# design.net
KiCad netlist of a schematic drawn in Altium Designer
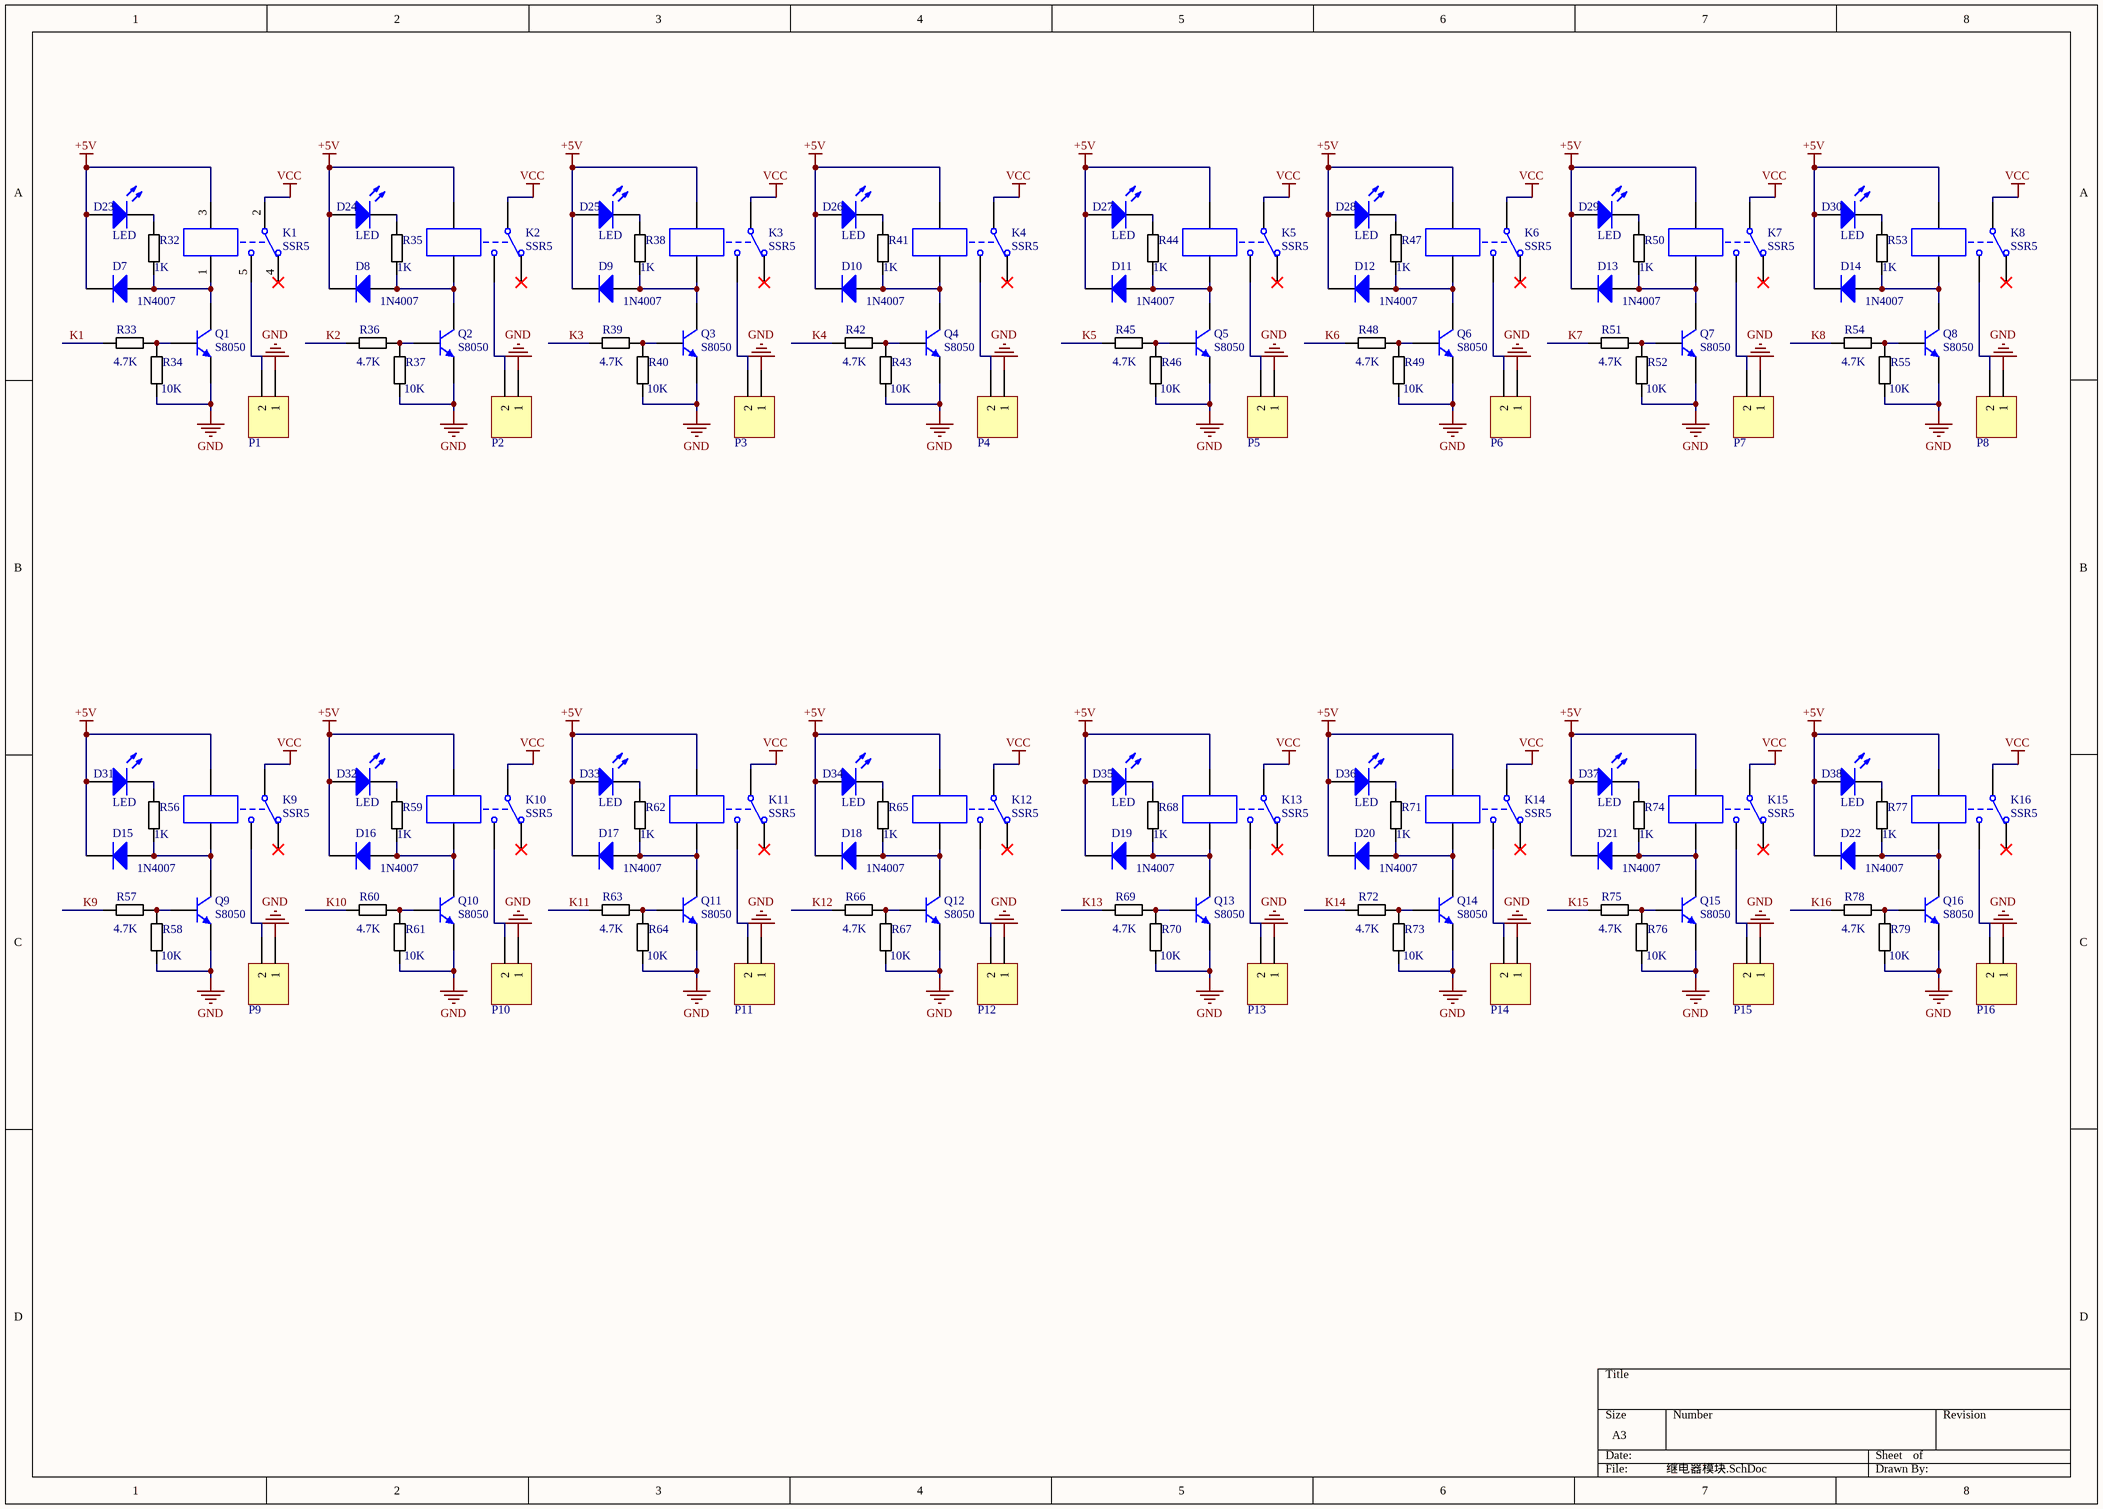
[diagram p0: 继电器模块.SchDoc]

(export (version "E")
  (design (tool "Eeschema 10.0.6"))
  (components
    (comp (ref "D7")
      (value "1N4007")
      (footprint "SMA")
      (description "1 Amp General Purpose Rectifier")
      (fields (field (name "PUBLISHER") "Altium Limited"))
      (libsource (lib "Sensor") (part "Diode 1N4007"))
    )
    (comp (ref "D8")
      (value "1N4007")
      (footprint "SMA")
      (description "1 Amp General Purpose Rectifier")
      (fields (field (name "PUBLISHER") "Altium Limited"))
      (libsource (lib "Sensor") (part "Diode 1N4007"))
    )
    (comp (ref "D9")
      (value "1N4007")
      (footprint "SMA")
      (description "1 Amp General Purpose Rectifier")
      (fields (field (name "PUBLISHER") "Altium Limited"))
      (libsource (lib "Sensor") (part "Diode 1N4007"))
    )
    (comp (ref "D10")
      (value "1N4007")
      (footprint "SMA")
      (description "1 Amp General Purpose Rectifier")
      (fields (field (name "PUBLISHER") "Altium Limited"))
      (libsource (lib "Sensor") (part "Diode 1N4007"))
    )
    (comp (ref "D11")
      (value "1N4007")
      (footprint "SMA")
      (description "1 Amp General Purpose Rectifier")
      (fields (field (name "PUBLISHER") "Altium Limited"))
      (libsource (lib "Sensor") (part "Diode 1N4007"))
    )
    (comp (ref "D12")
      (value "1N4007")
      (footprint "SMA")
      (description "1 Amp General Purpose Rectifier")
      (fields (field (name "PUBLISHER") "Altium Limited"))
      (libsource (lib "Sensor") (part "Diode 1N4007"))
    )
    (comp (ref "D13")
      (value "1N4007")
      (footprint "SMA")
      (description "1 Amp General Purpose Rectifier")
      (fields (field (name "PUBLISHER") "Altium Limited"))
      (libsource (lib "Sensor") (part "Diode 1N4007"))
    )
    (comp (ref "D14")
      (value "1N4007")
      (footprint "SMA")
      (description "1 Amp General Purpose Rectifier")
      (fields (field (name "PUBLISHER") "Altium Limited"))
      (libsource (lib "Sensor") (part "Diode 1N4007"))
    )
    (comp (ref "D15")
      (value "1N4007")
      (footprint "SMA")
      (description "1 Amp General Purpose Rectifier")
      (fields (field (name "PUBLISHER") "Altium Limited"))
      (libsource (lib "Sensor") (part "Diode 1N4007"))
    )
    (comp (ref "D16")
      (value "1N4007")
      (footprint "SMA")
      (description "1 Amp General Purpose Rectifier")
      (fields (field (name "PUBLISHER") "Altium Limited"))
      (libsource (lib "Sensor") (part "Diode 1N4007"))
    )
    (comp (ref "D17")
      (value "1N4007")
      (footprint "SMA")
      (description "1 Amp General Purpose Rectifier")
      (fields (field (name "PUBLISHER") "Altium Limited"))
      (libsource (lib "Sensor") (part "Diode 1N4007"))
    )
    (comp (ref "D18")
      (value "1N4007")
      (footprint "SMA")
      (description "1 Amp General Purpose Rectifier")
      (fields (field (name "PUBLISHER") "Altium Limited"))
      (libsource (lib "Sensor") (part "Diode 1N4007"))
    )
    (comp (ref "D19")
      (value "1N4007")
      (footprint "SMA")
      (description "1 Amp General Purpose Rectifier")
      (fields (field (name "PUBLISHER") "Altium Limited"))
      (libsource (lib "Sensor") (part "Diode 1N4007"))
    )
    (comp (ref "D20")
      (value "1N4007")
      (footprint "SMA")
      (description "1 Amp General Purpose Rectifier")
      (fields (field (name "PUBLISHER") "Altium Limited"))
      (libsource (lib "Sensor") (part "Diode 1N4007"))
    )
    (comp (ref "D21")
      (value "1N4007")
      (footprint "SMA")
      (description "1 Amp General Purpose Rectifier")
      (fields (field (name "PUBLISHER") "Altium Limited"))
      (libsource (lib "Sensor") (part "Diode 1N4007"))
    )
    (comp (ref "D22")
      (value "1N4007")
      (footprint "SMA")
      (description "1 Amp General Purpose Rectifier")
      (fields (field (name "PUBLISHER") "Altium Limited"))
      (libsource (lib "Sensor") (part "Diode 1N4007"))
    )
    (comp (ref "D23") (value "LED") (footprint "LED") (libsource (lib "Sensor") (part "LED")))
    (comp (ref "D24") (value "LED") (footprint "LED") (libsource (lib "Sensor") (part "LED")))
    (comp (ref "D25") (value "LED") (footprint "LED") (libsource (lib "Sensor") (part "LED")))
    (comp (ref "D26") (value "LED") (footprint "LED") (libsource (lib "Sensor") (part "LED")))
    (comp (ref "D27") (value "LED") (footprint "LED") (libsource (lib "Sensor") (part "LED")))
    (comp (ref "D28") (value "LED") (footprint "LED") (libsource (lib "Sensor") (part "LED")))
    (comp (ref "D29") (value "LED") (footprint "LED") (libsource (lib "Sensor") (part "LED")))
    (comp (ref "D30") (value "LED") (footprint "LED") (libsource (lib "Sensor") (part "LED")))
    (comp (ref "D31") (value "LED") (footprint "LED") (libsource (lib "Sensor") (part "LED")))
    (comp (ref "D32") (value "LED") (footprint "LED") (libsource (lib "Sensor") (part "LED")))
    (comp (ref "D33") (value "LED") (footprint "LED") (libsource (lib "Sensor") (part "LED")))
    (comp (ref "D34") (value "LED") (footprint "LED") (libsource (lib "Sensor") (part "LED")))
    (comp (ref "D35") (value "LED") (footprint "LED") (libsource (lib "Sensor") (part "LED")))
    (comp (ref "D36") (value "LED") (footprint "LED") (libsource (lib "Sensor") (part "LED")))
    (comp (ref "D37") (value "LED") (footprint "LED") (libsource (lib "Sensor") (part "LED")))
    (comp (ref "D38") (value "LED") (footprint "LED") (libsource (lib "Sensor") (part "LED")))
    (comp (ref "K1")
      (value "SSR5")
      (footprint "SSR-DC5")
      (fields (field (name "PUBLISHER") "Altium Limited"))
      (libsource (lib "") (part "SSR5_1"))
    )
    (comp (ref "K2")
      (value "SSR5")
      (footprint "SSR-DC5")
      (fields (field (name "PUBLISHER") "Altium Limited"))
      (libsource (lib "Power_5V_1A") (part "SSR5"))
    )
    (comp (ref "K3")
      (value "SSR5")
      (footprint "SSR-DC5")
      (fields (field (name "PUBLISHER") "Altium Limited"))
      (libsource (lib "Power_5V_1A") (part "SSR5"))
    )
    (comp (ref "K4")
      (value "SSR5")
      (footprint "SSR-DC5")
      (fields (field (name "PUBLISHER") "Altium Limited"))
      (libsource (lib "Power_5V_1A") (part "SSR5"))
    )
    (comp (ref "K5")
      (value "SSR5")
      (footprint "SSR-DC5")
      (fields (field (name "PUBLISHER") "Altium Limited"))
      (libsource (lib "Power_5V_1A") (part "SSR5"))
    )
    (comp (ref "K6")
      (value "SSR5")
      (footprint "SSR-DC5")
      (fields (field (name "PUBLISHER") "Altium Limited"))
      (libsource (lib "Power_5V_1A") (part "SSR5"))
    )
    (comp (ref "K7")
      (value "SSR5")
      (footprint "SSR-DC5")
      (fields (field (name "PUBLISHER") "Altium Limited"))
      (libsource (lib "Power_5V_1A") (part "SSR5"))
    )
    (comp (ref "K8")
      (value "SSR5")
      (footprint "SSR-DC5")
      (fields (field (name "PUBLISHER") "Altium Limited"))
      (libsource (lib "Power_5V_1A") (part "SSR5"))
    )
    (comp (ref "K9")
      (value "SSR5")
      (footprint "SSR-DC5")
      (fields (field (name "PUBLISHER") "Altium Limited"))
      (libsource (lib "Power_5V_1A") (part "SSR5"))
    )
    (comp (ref "K10")
      (value "SSR5")
      (footprint "SSR-DC5")
      (fields (field (name "PUBLISHER") "Altium Limited"))
      (libsource (lib "Power_5V_1A") (part "SSR5"))
    )
    (comp (ref "K11")
      (value "SSR5")
      (footprint "SSR-DC5")
      (fields (field (name "PUBLISHER") "Altium Limited"))
      (libsource (lib "Power_5V_1A") (part "SSR5"))
    )
    (comp (ref "K12")
      (value "SSR5")
      (footprint "SSR-DC5")
      (fields (field (name "PUBLISHER") "Altium Limited"))
      (libsource (lib "Power_5V_1A") (part "SSR5"))
    )
    (comp (ref "K13")
      (value "SSR5")
      (footprint "SSR-DC5")
      (fields (field (name "PUBLISHER") "Altium Limited"))
      (libsource (lib "Power_5V_1A") (part "SSR5"))
    )
    (comp (ref "K14")
      (value "SSR5")
      (footprint "SSR-DC5")
      (fields (field (name "PUBLISHER") "Altium Limited"))
      (libsource (lib "Power_5V_1A") (part "SSR5"))
    )
    (comp (ref "K15")
      (value "SSR5")
      (footprint "SSR-DC5")
      (fields (field (name "PUBLISHER") "Altium Limited"))
      (libsource (lib "Power_5V_1A") (part "SSR5"))
    )
    (comp (ref "K16")
      (value "SSR5")
      (footprint "SSR-DC5")
      (fields (field (name "PUBLISHER") "Altium Limited"))
      (libsource (lib "Power_5V_1A") (part "SSR5"))
    )
    (comp (ref "P1")
      (value "Header 2")
      (footprint "电源")
      (description "Header, 2-Pin")
      (fields (field (name "PUBLISHER") "Altium Limited"))
      (libsource (lib "Miscellaneous Connectors") (part "Header 2"))
    )
    (comp (ref "P2")
      (value "Header 2")
      (footprint "电源")
      (description "Header, 2-Pin")
      (fields (field (name "PUBLISHER") "Altium Limited"))
      (libsource (lib "Miscellaneous Connectors") (part "Header 2"))
    )
    (comp (ref "P3")
      (value "Header 2")
      (footprint "电源")
      (description "Header, 2-Pin")
      (fields (field (name "PUBLISHER") "Altium Limited"))
      (libsource (lib "Miscellaneous Connectors") (part "Header 2"))
    )
    (comp (ref "P4")
      (value "Header 2")
      (footprint "电源")
      (description "Header, 2-Pin")
      (fields (field (name "PUBLISHER") "Altium Limited"))
      (libsource (lib "Miscellaneous Connectors") (part "Header 2"))
    )
    (comp (ref "P5")
      (value "Header 2")
      (footprint "电源")
      (description "Header, 2-Pin")
      (fields (field (name "PUBLISHER") "Altium Limited"))
      (libsource (lib "Miscellaneous Connectors") (part "Header 2"))
    )
    (comp (ref "P6")
      (value "Header 2")
      (footprint "电源")
      (description "Header, 2-Pin")
      (fields (field (name "PUBLISHER") "Altium Limited"))
      (libsource (lib "Miscellaneous Connectors") (part "Header 2"))
    )
    (comp (ref "P7")
      (value "Header 2")
      (footprint "电源")
      (description "Header, 2-Pin")
      (fields (field (name "PUBLISHER") "Altium Limited"))
      (libsource (lib "Miscellaneous Connectors") (part "Header 2"))
    )
    (comp (ref "P8")
      (value "Header 2")
      (footprint "电源")
      (description "Header, 2-Pin")
      (fields (field (name "PUBLISHER") "Altium Limited"))
      (libsource (lib "Miscellaneous Connectors") (part "Header 2"))
    )
    (comp (ref "P9")
      (value "Header 2")
      (footprint "电源")
      (description "Header, 2-Pin")
      (fields (field (name "PUBLISHER") "Altium Limited"))
      (libsource (lib "Miscellaneous Connectors") (part "Header 2"))
    )
    (comp (ref "P10")
      (value "Header 2")
      (footprint "电源")
      (description "Header, 2-Pin")
      (fields (field (name "PUBLISHER") "Altium Limited"))
      (libsource (lib "Miscellaneous Connectors") (part "Header 2"))
    )
    (comp (ref "P11")
      (value "Header 2")
      (footprint "电源")
      (description "Header, 2-Pin")
      (fields (field (name "PUBLISHER") "Altium Limited"))
      (libsource (lib "Miscellaneous Connectors") (part "Header 2"))
    )
    (comp (ref "P12")
      (value "Header 2")
      (footprint "电源")
      (description "Header, 2-Pin")
      (fields (field (name "PUBLISHER") "Altium Limited"))
      (libsource (lib "Miscellaneous Connectors") (part "Header 2"))
    )
    (comp (ref "P13")
      (value "Header 2")
      (footprint "电源")
      (description "Header, 2-Pin")
      (fields (field (name "PUBLISHER") "Altium Limited"))
      (libsource (lib "Miscellaneous Connectors") (part "Header 2"))
    )
    (comp (ref "P14")
      (value "Header 2")
      (footprint "电源")
      (description "Header, 2-Pin")
      (fields (field (name "PUBLISHER") "Altium Limited"))
      (libsource (lib "Miscellaneous Connectors") (part "Header 2"))
    )
    (comp (ref "P15")
      (value "Header 2")
      (footprint "电源")
      (description "Header, 2-Pin")
      (fields (field (name "PUBLISHER") "Altium Limited"))
      (libsource (lib "Miscellaneous Connectors") (part "Header 2"))
    )
    (comp (ref "P16")
      (value "Header 2")
      (footprint "电源")
      (description "Header, 2-Pin")
      (fields (field (name "PUBLISHER") "Altium Limited"))
      (libsource (lib "Miscellaneous Connectors") (part "Header 2"))
    )
    (comp (ref "Q1") (value "S8050") (footprint "SOT-23") (libsource (lib "Sensor") (part "S8050")))
    (comp (ref "Q2") (value "S8050") (footprint "SOT-23") (libsource (lib "Sensor") (part "S8050")))
    (comp (ref "Q3") (value "S8050") (footprint "SOT-23") (libsource (lib "Sensor") (part "S8050")))
    (comp (ref "Q4") (value "S8050") (footprint "SOT-23") (libsource (lib "Sensor") (part "S8050")))
    (comp (ref "Q5") (value "S8050") (footprint "SOT-23") (libsource (lib "Sensor") (part "S8050")))
    (comp (ref "Q6") (value "S8050") (footprint "SOT-23") (libsource (lib "Sensor") (part "S8050")))
    (comp (ref "Q7") (value "S8050") (footprint "SOT-23") (libsource (lib "Sensor") (part "S8050")))
    (comp (ref "Q8") (value "S8050") (footprint "SOT-23") (libsource (lib "Sensor") (part "S8050")))
    (comp (ref "Q9") (value "S8050") (footprint "SOT-23") (libsource (lib "Sensor") (part "S8050")))
    (comp (ref "Q10") (value "S8050") (footprint "SOT-23") (libsource (lib "Sensor") (part "S8050")))
    (comp (ref "Q11") (value "S8050") (footprint "SOT-23") (libsource (lib "Sensor") (part "S8050")))
    (comp (ref "Q12") (value "S8050") (footprint "SOT-23") (libsource (lib "Sensor") (part "S8050")))
    (comp (ref "Q13") (value "S8050") (footprint "SOT-23") (libsource (lib "Sensor") (part "S8050")))
    (comp (ref "Q14") (value "S8050") (footprint "SOT-23") (libsource (lib "Sensor") (part "S8050")))
    (comp (ref "Q15") (value "S8050") (footprint "SOT-23") (libsource (lib "Sensor") (part "S8050")))
    (comp (ref "Q16") (value "S8050") (footprint "SOT-23") (libsource (lib "Sensor") (part "S8050")))
    (comp (ref "R32") (value "1K") (footprint "0603") (libsource (lib "") (part "RES-1K_2")))
    (comp (ref "R33") (value "4.7K") (footprint "0603") (libsource (lib "Sensor") (part "RES-1K")))
    (comp (ref "R34") (value "10K") (footprint "0603") (libsource (lib "") (part "RES-1K_1")))
    (comp (ref "R35") (value "1K") (footprint "0603") (libsource (lib "") (part "RES-1K_2")))
    (comp (ref "R36") (value "4.7K") (footprint "0603") (libsource (lib "Sensor") (part "RES-1K")))
    (comp (ref "R37") (value "10K") (footprint "0603") (libsource (lib "") (part "RES-1K_1")))
    (comp (ref "R38") (value "1K") (footprint "0603") (libsource (lib "") (part "RES-1K_2")))
    (comp (ref "R39") (value "4.7K") (footprint "0603") (libsource (lib "Sensor") (part "RES-1K")))
    (comp (ref "R40") (value "10K") (footprint "0603") (libsource (lib "") (part "RES-1K_1")))
    (comp (ref "R41") (value "1K") (footprint "0603") (libsource (lib "") (part "RES-1K_2")))
    (comp (ref "R42") (value "4.7K") (footprint "0603") (libsource (lib "Sensor") (part "RES-1K")))
    (comp (ref "R43") (value "10K") (footprint "0603") (libsource (lib "") (part "RES-1K_1")))
    (comp (ref "R44") (value "1K") (footprint "0603") (libsource (lib "") (part "RES-1K_2")))
    (comp (ref "R45") (value "4.7K") (footprint "0603") (libsource (lib "Sensor") (part "RES-1K")))
    (comp (ref "R46") (value "10K") (footprint "0603") (libsource (lib "") (part "RES-1K_1")))
    (comp (ref "R47") (value "1K") (footprint "0603") (libsource (lib "") (part "RES-1K_2")))
    (comp (ref "R48") (value "4.7K") (footprint "0603") (libsource (lib "Sensor") (part "RES-1K")))
    (comp (ref "R49") (value "10K") (footprint "0603") (libsource (lib "") (part "RES-1K_1")))
    (comp (ref "R50") (value "1K") (footprint "0603") (libsource (lib "") (part "RES-1K_2")))
    (comp (ref "R51") (value "4.7K") (footprint "0603") (libsource (lib "Sensor") (part "RES-1K")))
    (comp (ref "R52") (value "10K") (footprint "0603") (libsource (lib "") (part "RES-1K_1")))
    (comp (ref "R53") (value "1K") (footprint "0603") (libsource (lib "") (part "RES-1K_2")))
    (comp (ref "R54") (value "4.7K") (footprint "0603") (libsource (lib "Sensor") (part "RES-1K")))
    (comp (ref "R55") (value "10K") (footprint "0603") (libsource (lib "") (part "RES-1K_1")))
    (comp (ref "R56") (value "1K") (footprint "0603") (libsource (lib "") (part "RES-1K_2")))
    (comp (ref "R57") (value "4.7K") (footprint "0603") (libsource (lib "Sensor") (part "RES-1K")))
    (comp (ref "R58") (value "10K") (footprint "0603") (libsource (lib "") (part "RES-1K_1")))
    (comp (ref "R59") (value "1K") (footprint "0603") (libsource (lib "") (part "RES-1K_2")))
    (comp (ref "R60") (value "4.7K") (footprint "0603") (libsource (lib "Sensor") (part "RES-1K")))
    (comp (ref "R61") (value "10K") (footprint "0603") (libsource (lib "") (part "RES-1K_1")))
    (comp (ref "R62") (value "1K") (footprint "0603") (libsource (lib "") (part "RES-1K_2")))
    (comp (ref "R63") (value "4.7K") (footprint "0603") (libsource (lib "Sensor") (part "RES-1K")))
    (comp (ref "R64") (value "10K") (footprint "0603") (libsource (lib "") (part "RES-1K_1")))
    (comp (ref "R65") (value "1K") (footprint "0603") (libsource (lib "") (part "RES-1K_2")))
    (comp (ref "R66") (value "4.7K") (footprint "0603") (libsource (lib "Sensor") (part "RES-1K")))
    (comp (ref "R67") (value "10K") (footprint "0603") (libsource (lib "") (part "RES-1K_1")))
    (comp (ref "R68") (value "1K") (footprint "0603") (libsource (lib "") (part "RES-1K_2")))
    (comp (ref "R69") (value "4.7K") (footprint "0603") (libsource (lib "Sensor") (part "RES-1K")))
    (comp (ref "R70") (value "10K") (footprint "0603") (libsource (lib "") (part "RES-1K_1")))
    (comp (ref "R71") (value "1K") (footprint "0603") (libsource (lib "") (part "RES-1K_2")))
    (comp (ref "R72") (value "4.7K") (footprint "0603") (libsource (lib "Sensor") (part "RES-1K")))
    (comp (ref "R73") (value "10K") (footprint "0603") (libsource (lib "") (part "RES-1K_1")))
    (comp (ref "R74") (value "1K") (footprint "0603") (libsource (lib "") (part "RES-1K_2")))
    (comp (ref "R75") (value "4.7K") (footprint "0603") (libsource (lib "Sensor") (part "RES-1K")))
    (comp (ref "R76") (value "10K") (footprint "0603") (libsource (lib "") (part "RES-1K_1")))
    (comp (ref "R77") (value "1K") (footprint "0603") (libsource (lib "") (part "RES-1K_2")))
    (comp (ref "R78") (value "4.7K") (footprint "0603") (libsource (lib "Sensor") (part "RES-1K")))
    (comp (ref "R79") (value "10K") (footprint "0603") (libsource (lib "") (part "RES-1K_1")))
  )
  (nets
    (net (code "1") (name "+5V") (class "Default")
      (node (ref "D10") (pin "2") (pinfunction "K_2") (pintype "passive"))
      (node (ref "D11") (pin "2") (pinfunction "K_2") (pintype "passive"))
      (node (ref "D12") (pin "2") (pinfunction "K_2") (pintype "passive"))
      (node (ref "D13") (pin "2") (pinfunction "K_2") (pintype "passive"))
      (node (ref "D14") (pin "2") (pinfunction "K_2") (pintype "passive"))
      (node (ref "D15") (pin "2") (pinfunction "K_2") (pintype "passive"))
      (node (ref "D16") (pin "2") (pinfunction "K_2") (pintype "passive"))
      (node (ref "D17") (pin "2") (pinfunction "K_2") (pintype "passive"))
      (node (ref "D18") (pin "2") (pinfunction "K_2") (pintype "passive"))
      (node (ref "D19") (pin "2") (pinfunction "K_2") (pintype "passive"))
      (node (ref "D20") (pin "2") (pinfunction "K_2") (pintype "passive"))
      (node (ref "D21") (pin "2") (pinfunction "K_2") (pintype "passive"))
      (node (ref "D22") (pin "2") (pinfunction "K_2") (pintype "passive"))
      (node (ref "D23") (pin "1") (pinfunction "A_1") (pintype "passive"))
      (node (ref "D24") (pin "1") (pinfunction "A_1") (pintype "passive"))
      (node (ref "D25") (pin "1") (pinfunction "A_1") (pintype "passive"))
      (node (ref "D26") (pin "1") (pinfunction "A_1") (pintype "passive"))
      (node (ref "D27") (pin "1") (pinfunction "A_1") (pintype "passive"))
      (node (ref "D28") (pin "1") (pinfunction "A_1") (pintype "passive"))
      (node (ref "D29") (pin "1") (pinfunction "A_1") (pintype "passive"))
      (node (ref "D30") (pin "1") (pinfunction "A_1") (pintype "passive"))
      (node (ref "D31") (pin "1") (pinfunction "A_1") (pintype "passive"))
      (node (ref "D32") (pin "1") (pinfunction "A_1") (pintype "passive"))
      (node (ref "D33") (pin "1") (pinfunction "A_1") (pintype "passive"))
      (node (ref "D34") (pin "1") (pinfunction "A_1") (pintype "passive"))
      (node (ref "D35") (pin "1") (pinfunction "A_1") (pintype "passive"))
      (node (ref "D36") (pin "1") (pinfunction "A_1") (pintype "passive"))
      (node (ref "D37") (pin "1") (pinfunction "A_1") (pintype "passive"))
      (node (ref "D38") (pin "1") (pinfunction "A_1") (pintype "passive"))
      (node (ref "D7") (pin "2") (pinfunction "K_2") (pintype "passive"))
      (node (ref "D8") (pin "2") (pinfunction "K_2") (pintype "passive"))
      (node (ref "D9") (pin "2") (pinfunction "K_2") (pintype "passive"))
      (node (ref "K1") (pin "3") (pinfunction "3_3") (pintype "passive"))
      (node (ref "K10") (pin "3") (pinfunction "3_3") (pintype "passive"))
      (node (ref "K11") (pin "3") (pinfunction "3_3") (pintype "passive"))
      (node (ref "K12") (pin "3") (pinfunction "3_3") (pintype "passive"))
      (node (ref "K13") (pin "3") (pinfunction "3_3") (pintype "passive"))
      (node (ref "K14") (pin "3") (pinfunction "3_3") (pintype "passive"))
      (node (ref "K15") (pin "3") (pinfunction "3_3") (pintype "passive"))
      (node (ref "K16") (pin "3") (pinfunction "3_3") (pintype "passive"))
      (node (ref "K2") (pin "3") (pinfunction "3_3") (pintype "passive"))
      (node (ref "K3") (pin "3") (pinfunction "3_3") (pintype "passive"))
      (node (ref "K4") (pin "3") (pinfunction "3_3") (pintype "passive"))
      (node (ref "K5") (pin "3") (pinfunction "3_3") (pintype "passive"))
      (node (ref "K6") (pin "3") (pinfunction "3_3") (pintype "passive"))
      (node (ref "K7") (pin "3") (pinfunction "3_3") (pintype "passive"))
      (node (ref "K8") (pin "3") (pinfunction "3_3") (pintype "passive"))
      (node (ref "K9") (pin "3") (pinfunction "3_3") (pintype "passive"))
    )
    (net (code "2") (name "/K1") (class "Default")
      (node (ref "R33") (pin "2") (pinfunction "2_2") (pintype "passive"))
    )
    (net (code "3") (name "/K2") (class "Default")
      (node (ref "R36") (pin "2") (pinfunction "2_2") (pintype "passive"))
    )
    (net (code "4") (name "/K3") (class "Default")
      (node (ref "R39") (pin "2") (pinfunction "2_2") (pintype "passive"))
    )
    (net (code "5") (name "/K4") (class "Default")
      (node (ref "R42") (pin "2") (pinfunction "2_2") (pintype "passive"))
    )
    (net (code "6") (name "/K5") (class "Default")
      (node (ref "R45") (pin "2") (pinfunction "2_2") (pintype "passive"))
    )
    (net (code "7") (name "/K6") (class "Default")
      (node (ref "R48") (pin "2") (pinfunction "2_2") (pintype "passive"))
    )
    (net (code "8") (name "/K7") (class "Default")
      (node (ref "R51") (pin "2") (pinfunction "2_2") (pintype "passive"))
    )
    (net (code "9") (name "/K8") (class "Default")
      (node (ref "R54") (pin "2") (pinfunction "2_2") (pintype "passive"))
    )
    (net (code "10") (name "/K9") (class "Default")
      (node (ref "R57") (pin "2") (pinfunction "2_2") (pintype "passive"))
    )
    (net (code "11") (name "/K10") (class "Default")
      (node (ref "R60") (pin "2") (pinfunction "2_2") (pintype "passive"))
    )
    (net (code "12") (name "/K11") (class "Default")
      (node (ref "R63") (pin "2") (pinfunction "2_2") (pintype "passive"))
    )
    (net (code "13") (name "/K12") (class "Default")
      (node (ref "R66") (pin "2") (pinfunction "2_2") (pintype "passive"))
    )
    (net (code "14") (name "/K13") (class "Default")
      (node (ref "R69") (pin "2") (pinfunction "2_2") (pintype "passive"))
    )
    (net (code "15") (name "/K14") (class "Default")
      (node (ref "R72") (pin "2") (pinfunction "2_2") (pintype "passive"))
    )
    (net (code "16") (name "/K15") (class "Default")
      (node (ref "R75") (pin "2") (pinfunction "2_2") (pintype "passive"))
    )
    (net (code "17") (name "/K16") (class "Default")
      (node (ref "R78") (pin "2") (pinfunction "2_2") (pintype "passive"))
    )
    (net (code "18") (name "GND") (class "Default")
      (node (ref "P1") (pin "1") (pinfunction "1_1") (pintype "passive"))
      (node (ref "P10") (pin "1") (pinfunction "1_1") (pintype "passive"))
      (node (ref "P11") (pin "1") (pinfunction "1_1") (pintype "passive"))
      (node (ref "P12") (pin "1") (pinfunction "1_1") (pintype "passive"))
      (node (ref "P13") (pin "1") (pinfunction "1_1") (pintype "passive"))
      (node (ref "P14") (pin "1") (pinfunction "1_1") (pintype "passive"))
      (node (ref "P15") (pin "1") (pinfunction "1_1") (pintype "passive"))
      (node (ref "P16") (pin "1") (pinfunction "1_1") (pintype "passive"))
      (node (ref "P2") (pin "1") (pinfunction "1_1") (pintype "passive"))
      (node (ref "P3") (pin "1") (pinfunction "1_1") (pintype "passive"))
      (node (ref "P4") (pin "1") (pinfunction "1_1") (pintype "passive"))
      (node (ref "P5") (pin "1") (pinfunction "1_1") (pintype "passive"))
      (node (ref "P6") (pin "1") (pinfunction "1_1") (pintype "passive"))
      (node (ref "P7") (pin "1") (pinfunction "1_1") (pintype "passive"))
      (node (ref "P8") (pin "1") (pinfunction "1_1") (pintype "passive"))
      (node (ref "P9") (pin "1") (pinfunction "1_1") (pintype "passive"))
      (node (ref "Q1") (pin "2") (pinfunction "E_2") (pintype "passive"))
      (node (ref "Q10") (pin "2") (pinfunction "E_2") (pintype "passive"))
      (node (ref "Q11") (pin "2") (pinfunction "E_2") (pintype "passive"))
      (node (ref "Q12") (pin "2") (pinfunction "E_2") (pintype "passive"))
      (node (ref "Q13") (pin "2") (pinfunction "E_2") (pintype "passive"))
      (node (ref "Q14") (pin "2") (pinfunction "E_2") (pintype "passive"))
      (node (ref "Q15") (pin "2") (pinfunction "E_2") (pintype "passive"))
      (node (ref "Q16") (pin "2") (pinfunction "E_2") (pintype "passive"))
      (node (ref "Q2") (pin "2") (pinfunction "E_2") (pintype "passive"))
      (node (ref "Q3") (pin "2") (pinfunction "E_2") (pintype "passive"))
      (node (ref "Q4") (pin "2") (pinfunction "E_2") (pintype "passive"))
      (node (ref "Q5") (pin "2") (pinfunction "E_2") (pintype "passive"))
      (node (ref "Q6") (pin "2") (pinfunction "E_2") (pintype "passive"))
      (node (ref "Q7") (pin "2") (pinfunction "E_2") (pintype "passive"))
      (node (ref "Q8") (pin "2") (pinfunction "E_2") (pintype "passive"))
      (node (ref "Q9") (pin "2") (pinfunction "E_2") (pintype "passive"))
      (node (ref "R34") (pin "2") (pinfunction "2_2") (pintype "passive"))
      (node (ref "R37") (pin "2") (pinfunction "2_2") (pintype "passive"))
      (node (ref "R40") (pin "2") (pinfunction "2_2") (pintype "passive"))
      (node (ref "R43") (pin "2") (pinfunction "2_2") (pintype "passive"))
      (node (ref "R46") (pin "2") (pinfunction "2_2") (pintype "passive"))
      (node (ref "R49") (pin "2") (pinfunction "2_2") (pintype "passive"))
      (node (ref "R52") (pin "2") (pinfunction "2_2") (pintype "passive"))
      (node (ref "R55") (pin "2") (pinfunction "2_2") (pintype "passive"))
      (node (ref "R58") (pin "2") (pinfunction "2_2") (pintype "passive"))
      (node (ref "R61") (pin "2") (pinfunction "2_2") (pintype "passive"))
      (node (ref "R64") (pin "2") (pinfunction "2_2") (pintype "passive"))
      (node (ref "R67") (pin "2") (pinfunction "2_2") (pintype "passive"))
      (node (ref "R70") (pin "2") (pinfunction "2_2") (pintype "passive"))
      (node (ref "R73") (pin "2") (pinfunction "2_2") (pintype "passive"))
      (node (ref "R76") (pin "2") (pinfunction "2_2") (pintype "passive"))
      (node (ref "R79") (pin "2") (pinfunction "2_2") (pintype "passive"))
    )
    (net (code "19") (name "Net-(D7-A)") (class "Default")
      (node (ref "D7") (pin "1") (pinfunction "A_1") (pintype "passive"))
      (node (ref "K1") (pin "1") (pinfunction "1_1") (pintype "passive"))
      (node (ref "Q1") (pin "3") (pinfunction "C_3") (pintype "passive"))
      (node (ref "R32") (pin "1") (pinfunction "1_1") (pintype "passive"))
    )
    (net (code "20") (name "Net-(D8-A)") (class "Default")
      (node (ref "D8") (pin "1") (pinfunction "A_1") (pintype "passive"))
      (node (ref "K2") (pin "1") (pinfunction "1_1") (pintype "passive"))
      (node (ref "Q2") (pin "3") (pinfunction "C_3") (pintype "passive"))
      (node (ref "R35") (pin "1") (pinfunction "1_1") (pintype "passive"))
    )
    (net (code "21") (name "Net-(D9-A)") (class "Default")
      (node (ref "D9") (pin "1") (pinfunction "A_1") (pintype "passive"))
      (node (ref "K3") (pin "1") (pinfunction "1_1") (pintype "passive"))
      (node (ref "Q3") (pin "3") (pinfunction "C_3") (pintype "passive"))
      (node (ref "R38") (pin "1") (pinfunction "1_1") (pintype "passive"))
    )
    (net (code "22") (name "Net-(D10-A)") (class "Default")
      (node (ref "D10") (pin "1") (pinfunction "A_1") (pintype "passive"))
      (node (ref "K4") (pin "1") (pinfunction "1_1") (pintype "passive"))
      (node (ref "Q4") (pin "3") (pinfunction "C_3") (pintype "passive"))
      (node (ref "R41") (pin "1") (pinfunction "1_1") (pintype "passive"))
    )
    (net (code "23") (name "Net-(D11-A)") (class "Default")
      (node (ref "D11") (pin "1") (pinfunction "A_1") (pintype "passive"))
      (node (ref "K5") (pin "1") (pinfunction "1_1") (pintype "passive"))
      (node (ref "Q5") (pin "3") (pinfunction "C_3") (pintype "passive"))
      (node (ref "R44") (pin "1") (pinfunction "1_1") (pintype "passive"))
    )
    (net (code "24") (name "Net-(D12-A)") (class "Default")
      (node (ref "D12") (pin "1") (pinfunction "A_1") (pintype "passive"))
      (node (ref "K6") (pin "1") (pinfunction "1_1") (pintype "passive"))
      (node (ref "Q6") (pin "3") (pinfunction "C_3") (pintype "passive"))
      (node (ref "R47") (pin "1") (pinfunction "1_1") (pintype "passive"))
    )
    (net (code "25") (name "Net-(D13-A)") (class "Default")
      (node (ref "D13") (pin "1") (pinfunction "A_1") (pintype "passive"))
      (node (ref "K7") (pin "1") (pinfunction "1_1") (pintype "passive"))
      (node (ref "Q7") (pin "3") (pinfunction "C_3") (pintype "passive"))
      (node (ref "R50") (pin "1") (pinfunction "1_1") (pintype "passive"))
    )
    (net (code "26") (name "Net-(D14-A)") (class "Default")
      (node (ref "D14") (pin "1") (pinfunction "A_1") (pintype "passive"))
      (node (ref "K8") (pin "1") (pinfunction "1_1") (pintype "passive"))
      (node (ref "Q8") (pin "3") (pinfunction "C_3") (pintype "passive"))
      (node (ref "R53") (pin "1") (pinfunction "1_1") (pintype "passive"))
    )
    (net (code "27") (name "Net-(D15-A)") (class "Default")
      (node (ref "D15") (pin "1") (pinfunction "A_1") (pintype "passive"))
      (node (ref "K9") (pin "1") (pinfunction "1_1") (pintype "passive"))
      (node (ref "Q9") (pin "3") (pinfunction "C_3") (pintype "passive"))
      (node (ref "R56") (pin "1") (pinfunction "1_1") (pintype "passive"))
    )
    (net (code "28") (name "Net-(D16-A)") (class "Default")
      (node (ref "D16") (pin "1") (pinfunction "A_1") (pintype "passive"))
      (node (ref "K10") (pin "1") (pinfunction "1_1") (pintype "passive"))
      (node (ref "Q10") (pin "3") (pinfunction "C_3") (pintype "passive"))
      (node (ref "R59") (pin "1") (pinfunction "1_1") (pintype "passive"))
    )
    (net (code "29") (name "Net-(D17-A)") (class "Default")
      (node (ref "D17") (pin "1") (pinfunction "A_1") (pintype "passive"))
      (node (ref "K11") (pin "1") (pinfunction "1_1") (pintype "passive"))
      (node (ref "Q11") (pin "3") (pinfunction "C_3") (pintype "passive"))
      (node (ref "R62") (pin "1") (pinfunction "1_1") (pintype "passive"))
    )
    (net (code "30") (name "Net-(D18-A)") (class "Default")
      (node (ref "D18") (pin "1") (pinfunction "A_1") (pintype "passive"))
      (node (ref "K12") (pin "1") (pinfunction "1_1") (pintype "passive"))
      (node (ref "Q12") (pin "3") (pinfunction "C_3") (pintype "passive"))
      (node (ref "R65") (pin "1") (pinfunction "1_1") (pintype "passive"))
    )
    (net (code "31") (name "Net-(D19-A)") (class "Default")
      (node (ref "D19") (pin "1") (pinfunction "A_1") (pintype "passive"))
      (node (ref "K13") (pin "1") (pinfunction "1_1") (pintype "passive"))
      (node (ref "Q13") (pin "3") (pinfunction "C_3") (pintype "passive"))
      (node (ref "R68") (pin "1") (pinfunction "1_1") (pintype "passive"))
    )
    (net (code "32") (name "Net-(D20-A)") (class "Default")
      (node (ref "D20") (pin "1") (pinfunction "A_1") (pintype "passive"))
      (node (ref "K14") (pin "1") (pinfunction "1_1") (pintype "passive"))
      (node (ref "Q14") (pin "3") (pinfunction "C_3") (pintype "passive"))
      (node (ref "R71") (pin "1") (pinfunction "1_1") (pintype "passive"))
    )
    (net (code "33") (name "Net-(D21-A)") (class "Default")
      (node (ref "D21") (pin "1") (pinfunction "A_1") (pintype "passive"))
      (node (ref "K15") (pin "1") (pinfunction "1_1") (pintype "passive"))
      (node (ref "Q15") (pin "3") (pinfunction "C_3") (pintype "passive"))
      (node (ref "R74") (pin "1") (pinfunction "1_1") (pintype "passive"))
    )
    (net (code "34") (name "Net-(D22-A)") (class "Default")
      (node (ref "D22") (pin "1") (pinfunction "A_1") (pintype "passive"))
      (node (ref "K16") (pin "1") (pinfunction "1_1") (pintype "passive"))
      (node (ref "Q16") (pin "3") (pinfunction "C_3") (pintype "passive"))
      (node (ref "R77") (pin "1") (pinfunction "1_1") (pintype "passive"))
    )
    (net (code "35") (name "Net-(D23-K)") (class "Default")
      (node (ref "D23") (pin "2") (pinfunction "K_2") (pintype "passive"))
      (node (ref "R32") (pin "2") (pinfunction "2_2") (pintype "passive"))
    )
    (net (code "36") (name "Net-(D24-K)") (class "Default")
      (node (ref "D24") (pin "2") (pinfunction "K_2") (pintype "passive"))
      (node (ref "R35") (pin "2") (pinfunction "2_2") (pintype "passive"))
    )
    (net (code "37") (name "Net-(D25-K)") (class "Default")
      (node (ref "D25") (pin "2") (pinfunction "K_2") (pintype "passive"))
      (node (ref "R38") (pin "2") (pinfunction "2_2") (pintype "passive"))
    )
    (net (code "38") (name "Net-(D26-K)") (class "Default")
      (node (ref "D26") (pin "2") (pinfunction "K_2") (pintype "passive"))
      (node (ref "R41") (pin "2") (pinfunction "2_2") (pintype "passive"))
    )
    (net (code "39") (name "Net-(D27-K)") (class "Default")
      (node (ref "D27") (pin "2") (pinfunction "K_2") (pintype "passive"))
      (node (ref "R44") (pin "2") (pinfunction "2_2") (pintype "passive"))
    )
    (net (code "40") (name "Net-(D28-K)") (class "Default")
      (node (ref "D28") (pin "2") (pinfunction "K_2") (pintype "passive"))
      (node (ref "R47") (pin "2") (pinfunction "2_2") (pintype "passive"))
    )
    (net (code "41") (name "Net-(D29-K)") (class "Default")
      (node (ref "D29") (pin "2") (pinfunction "K_2") (pintype "passive"))
      (node (ref "R50") (pin "2") (pinfunction "2_2") (pintype "passive"))
    )
    (net (code "42") (name "Net-(D30-K)") (class "Default")
      (node (ref "D30") (pin "2") (pinfunction "K_2") (pintype "passive"))
      (node (ref "R53") (pin "2") (pinfunction "2_2") (pintype "passive"))
    )
    (net (code "43") (name "Net-(D31-K)") (class "Default")
      (node (ref "D31") (pin "2") (pinfunction "K_2") (pintype "passive"))
      (node (ref "R56") (pin "2") (pinfunction "2_2") (pintype "passive"))
    )
    (net (code "44") (name "Net-(D32-K)") (class "Default")
      (node (ref "D32") (pin "2") (pinfunction "K_2") (pintype "passive"))
      (node (ref "R59") (pin "2") (pinfunction "2_2") (pintype "passive"))
    )
    (net (code "45") (name "Net-(D33-K)") (class "Default")
      (node (ref "D33") (pin "2") (pinfunction "K_2") (pintype "passive"))
      (node (ref "R62") (pin "2") (pinfunction "2_2") (pintype "passive"))
    )
    (net (code "46") (name "Net-(D34-K)") (class "Default")
      (node (ref "D34") (pin "2") (pinfunction "K_2") (pintype "passive"))
      (node (ref "R65") (pin "2") (pinfunction "2_2") (pintype "passive"))
    )
    (net (code "47") (name "Net-(D35-K)") (class "Default")
      (node (ref "D35") (pin "2") (pinfunction "K_2") (pintype "passive"))
      (node (ref "R68") (pin "2") (pinfunction "2_2") (pintype "passive"))
    )
    (net (code "48") (name "Net-(D36-K)") (class "Default")
      (node (ref "D36") (pin "2") (pinfunction "K_2") (pintype "passive"))
      (node (ref "R71") (pin "2") (pinfunction "2_2") (pintype "passive"))
    )
    (net (code "49") (name "Net-(D37-K)") (class "Default")
      (node (ref "D37") (pin "2") (pinfunction "K_2") (pintype "passive"))
      (node (ref "R74") (pin "2") (pinfunction "2_2") (pintype "passive"))
    )
    (net (code "50") (name "Net-(D38-K)") (class "Default")
      (node (ref "D38") (pin "2") (pinfunction "K_2") (pintype "passive"))
      (node (ref "R77") (pin "2") (pinfunction "2_2") (pintype "passive"))
    )
    (net (code "51") (name "Net-(K1-Pad5)") (class "Default")
      (node (ref "K1") (pin "5") (pinfunction "5_5") (pintype "passive"))
      (node (ref "P1") (pin "2") (pinfunction "2_2") (pintype "passive"))
    )
    (net (code "52") (name "Net-(K2-Pad5)") (class "Default")
      (node (ref "K2") (pin "5") (pinfunction "5_5") (pintype "passive"))
      (node (ref "P2") (pin "2") (pinfunction "2_2") (pintype "passive"))
    )
    (net (code "53") (name "Net-(K3-Pad5)") (class "Default")
      (node (ref "K3") (pin "5") (pinfunction "5_5") (pintype "passive"))
      (node (ref "P3") (pin "2") (pinfunction "2_2") (pintype "passive"))
    )
    (net (code "54") (name "Net-(K4-Pad5)") (class "Default")
      (node (ref "K4") (pin "5") (pinfunction "5_5") (pintype "passive"))
      (node (ref "P4") (pin "2") (pinfunction "2_2") (pintype "passive"))
    )
    (net (code "55") (name "Net-(K5-Pad5)") (class "Default")
      (node (ref "K5") (pin "5") (pinfunction "5_5") (pintype "passive"))
      (node (ref "P5") (pin "2") (pinfunction "2_2") (pintype "passive"))
    )
    (net (code "56") (name "Net-(K6-Pad5)") (class "Default")
      (node (ref "K6") (pin "5") (pinfunction "5_5") (pintype "passive"))
      (node (ref "P6") (pin "2") (pinfunction "2_2") (pintype "passive"))
    )
    (net (code "57") (name "Net-(K7-Pad5)") (class "Default")
      (node (ref "K7") (pin "5") (pinfunction "5_5") (pintype "passive"))
      (node (ref "P7") (pin "2") (pinfunction "2_2") (pintype "passive"))
    )
    (net (code "58") (name "Net-(K8-Pad5)") (class "Default")
      (node (ref "K8") (pin "5") (pinfunction "5_5") (pintype "passive"))
      (node (ref "P8") (pin "2") (pinfunction "2_2") (pintype "passive"))
    )
    (net (code "59") (name "Net-(K9-Pad5)") (class "Default")
      (node (ref "K9") (pin "5") (pinfunction "5_5") (pintype "passive"))
      (node (ref "P9") (pin "2") (pinfunction "2_2") (pintype "passive"))
    )
    (net (code "60") (name "Net-(K10-Pad5)") (class "Default")
      (node (ref "K10") (pin "5") (pinfunction "5_5") (pintype "passive"))
      (node (ref "P10") (pin "2") (pinfunction "2_2") (pintype "passive"))
    )
    (net (code "61") (name "Net-(K11-Pad5)") (class "Default")
      (node (ref "K11") (pin "5") (pinfunction "5_5") (pintype "passive"))
      (node (ref "P11") (pin "2") (pinfunction "2_2") (pintype "passive"))
    )
    (net (code "62") (name "Net-(K12-Pad5)") (class "Default")
      (node (ref "K12") (pin "5") (pinfunction "5_5") (pintype "passive"))
      (node (ref "P12") (pin "2") (pinfunction "2_2") (pintype "passive"))
    )
    (net (code "63") (name "Net-(K13-Pad5)") (class "Default")
      (node (ref "K13") (pin "5") (pinfunction "5_5") (pintype "passive"))
      (node (ref "P13") (pin "2") (pinfunction "2_2") (pintype "passive"))
    )
    (net (code "64") (name "Net-(K14-Pad5)") (class "Default")
      (node (ref "K14") (pin "5") (pinfunction "5_5") (pintype "passive"))
      (node (ref "P14") (pin "2") (pinfunction "2_2") (pintype "passive"))
    )
    (net (code "65") (name "Net-(K15-Pad5)") (class "Default")
      (node (ref "K15") (pin "5") (pinfunction "5_5") (pintype "passive"))
      (node (ref "P15") (pin "2") (pinfunction "2_2") (pintype "passive"))
    )
    (net (code "66") (name "Net-(K16-Pad5)") (class "Default")
      (node (ref "K16") (pin "5") (pinfunction "5_5") (pintype "passive"))
      (node (ref "P16") (pin "2") (pinfunction "2_2") (pintype "passive"))
    )
    (net (code "67") (name "Net-(Q1-B)") (class "Default")
      (node (ref "Q1") (pin "1") (pinfunction "B_1") (pintype "passive"))
      (node (ref "R33") (pin "1") (pinfunction "1_1") (pintype "passive"))
      (node (ref "R34") (pin "1") (pinfunction "1_1") (pintype "passive"))
    )
    (net (code "68") (name "Net-(Q2-B)") (class "Default")
      (node (ref "Q2") (pin "1") (pinfunction "B_1") (pintype "passive"))
      (node (ref "R36") (pin "1") (pinfunction "1_1") (pintype "passive"))
      (node (ref "R37") (pin "1") (pinfunction "1_1") (pintype "passive"))
    )
    (net (code "69") (name "Net-(Q3-B)") (class "Default")
      (node (ref "Q3") (pin "1") (pinfunction "B_1") (pintype "passive"))
      (node (ref "R39") (pin "1") (pinfunction "1_1") (pintype "passive"))
      (node (ref "R40") (pin "1") (pinfunction "1_1") (pintype "passive"))
    )
    (net (code "70") (name "Net-(Q4-B)") (class "Default")
      (node (ref "Q4") (pin "1") (pinfunction "B_1") (pintype "passive"))
      (node (ref "R42") (pin "1") (pinfunction "1_1") (pintype "passive"))
      (node (ref "R43") (pin "1") (pinfunction "1_1") (pintype "passive"))
    )
    (net (code "71") (name "Net-(Q5-B)") (class "Default")
      (node (ref "Q5") (pin "1") (pinfunction "B_1") (pintype "passive"))
      (node (ref "R45") (pin "1") (pinfunction "1_1") (pintype "passive"))
      (node (ref "R46") (pin "1") (pinfunction "1_1") (pintype "passive"))
    )
    (net (code "72") (name "Net-(Q6-B)") (class "Default")
      (node (ref "Q6") (pin "1") (pinfunction "B_1") (pintype "passive"))
      (node (ref "R48") (pin "1") (pinfunction "1_1") (pintype "passive"))
      (node (ref "R49") (pin "1") (pinfunction "1_1") (pintype "passive"))
    )
    (net (code "73") (name "Net-(Q7-B)") (class "Default")
      (node (ref "Q7") (pin "1") (pinfunction "B_1") (pintype "passive"))
      (node (ref "R51") (pin "1") (pinfunction "1_1") (pintype "passive"))
      (node (ref "R52") (pin "1") (pinfunction "1_1") (pintype "passive"))
    )
    (net (code "74") (name "Net-(Q8-B)") (class "Default")
      (node (ref "Q8") (pin "1") (pinfunction "B_1") (pintype "passive"))
      (node (ref "R54") (pin "1") (pinfunction "1_1") (pintype "passive"))
      (node (ref "R55") (pin "1") (pinfunction "1_1") (pintype "passive"))
    )
    (net (code "75") (name "Net-(Q9-B)") (class "Default")
      (node (ref "Q9") (pin "1") (pinfunction "B_1") (pintype "passive"))
      (node (ref "R57") (pin "1") (pinfunction "1_1") (pintype "passive"))
      (node (ref "R58") (pin "1") (pinfunction "1_1") (pintype "passive"))
    )
    (net (code "76") (name "Net-(Q10-B)") (class "Default")
      (node (ref "Q10") (pin "1") (pinfunction "B_1") (pintype "passive"))
      (node (ref "R60") (pin "1") (pinfunction "1_1") (pintype "passive"))
      (node (ref "R61") (pin "1") (pinfunction "1_1") (pintype "passive"))
    )
    (net (code "77") (name "Net-(Q11-B)") (class "Default")
      (node (ref "Q11") (pin "1") (pinfunction "B_1") (pintype "passive"))
      (node (ref "R63") (pin "1") (pinfunction "1_1") (pintype "passive"))
      (node (ref "R64") (pin "1") (pinfunction "1_1") (pintype "passive"))
    )
    (net (code "78") (name "Net-(Q12-B)") (class "Default")
      (node (ref "Q12") (pin "1") (pinfunction "B_1") (pintype "passive"))
      (node (ref "R66") (pin "1") (pinfunction "1_1") (pintype "passive"))
      (node (ref "R67") (pin "1") (pinfunction "1_1") (pintype "passive"))
    )
    (net (code "79") (name "Net-(Q13-B)") (class "Default")
      (node (ref "Q13") (pin "1") (pinfunction "B_1") (pintype "passive"))
      (node (ref "R69") (pin "1") (pinfunction "1_1") (pintype "passive"))
      (node (ref "R70") (pin "1") (pinfunction "1_1") (pintype "passive"))
    )
    (net (code "80") (name "Net-(Q14-B)") (class "Default")
      (node (ref "Q14") (pin "1") (pinfunction "B_1") (pintype "passive"))
      (node (ref "R72") (pin "1") (pinfunction "1_1") (pintype "passive"))
      (node (ref "R73") (pin "1") (pinfunction "1_1") (pintype "passive"))
    )
    (net (code "81") (name "Net-(Q15-B)") (class "Default")
      (node (ref "Q15") (pin "1") (pinfunction "B_1") (pintype "passive"))
      (node (ref "R75") (pin "1") (pinfunction "1_1") (pintype "passive"))
      (node (ref "R76") (pin "1") (pinfunction "1_1") (pintype "passive"))
    )
    (net (code "82") (name "Net-(Q16-B)") (class "Default")
      (node (ref "Q16") (pin "1") (pinfunction "B_1") (pintype "passive"))
      (node (ref "R78") (pin "1") (pinfunction "1_1") (pintype "passive"))
      (node (ref "R79") (pin "1") (pinfunction "1_1") (pintype "passive"))
    )
    (net (code "83") (name "VCC") (class "Default")
      (node (ref "K1") (pin "2") (pinfunction "2_2") (pintype "passive"))
      (node (ref "K10") (pin "2") (pinfunction "2_2") (pintype "passive"))
      (node (ref "K11") (pin "2") (pinfunction "2_2") (pintype "passive"))
      (node (ref "K12") (pin "2") (pinfunction "2_2") (pintype "passive"))
      (node (ref "K13") (pin "2") (pinfunction "2_2") (pintype "passive"))
      (node (ref "K14") (pin "2") (pinfunction "2_2") (pintype "passive"))
      (node (ref "K15") (pin "2") (pinfunction "2_2") (pintype "passive"))
      (node (ref "K16") (pin "2") (pinfunction "2_2") (pintype "passive"))
      (node (ref "K2") (pin "2") (pinfunction "2_2") (pintype "passive"))
      (node (ref "K3") (pin "2") (pinfunction "2_2") (pintype "passive"))
      (node (ref "K4") (pin "2") (pinfunction "2_2") (pintype "passive"))
      (node (ref "K5") (pin "2") (pinfunction "2_2") (pintype "passive"))
      (node (ref "K6") (pin "2") (pinfunction "2_2") (pintype "passive"))
      (node (ref "K7") (pin "2") (pinfunction "2_2") (pintype "passive"))
      (node (ref "K8") (pin "2") (pinfunction "2_2") (pintype "passive"))
      (node (ref "K9") (pin "2") (pinfunction "2_2") (pintype "passive"))
    )
    (net (code "84") (name "unconnected-(K1-Pad4)") (class "Default")
      (node (ref "K1") (pin "4") (pinfunction "4_4") (pintype "passive+no_connect"))
    )
    (net (code "85") (name "unconnected-(K2-Pad4)") (class "Default")
      (node (ref "K2") (pin "4") (pinfunction "4_4") (pintype "passive+no_connect"))
    )
    (net (code "86") (name "unconnected-(K3-Pad4)") (class "Default")
      (node (ref "K3") (pin "4") (pinfunction "4_4") (pintype "passive+no_connect"))
    )
    (net (code "87") (name "unconnected-(K4-Pad4)") (class "Default")
      (node (ref "K4") (pin "4") (pinfunction "4_4") (pintype "passive+no_connect"))
    )
    (net (code "88") (name "unconnected-(K5-Pad4)") (class "Default")
      (node (ref "K5") (pin "4") (pinfunction "4_4") (pintype "passive+no_connect"))
    )
    (net (code "89") (name "unconnected-(K6-Pad4)") (class "Default")
      (node (ref "K6") (pin "4") (pinfunction "4_4") (pintype "passive+no_connect"))
    )
    (net (code "90") (name "unconnected-(K7-Pad4)") (class "Default")
      (node (ref "K7") (pin "4") (pinfunction "4_4") (pintype "passive+no_connect"))
    )
    (net (code "91") (name "unconnected-(K8-Pad4)") (class "Default")
      (node (ref "K8") (pin "4") (pinfunction "4_4") (pintype "passive+no_connect"))
    )
    (net (code "92") (name "unconnected-(K9-Pad4)") (class "Default")
      (node (ref "K9") (pin "4") (pinfunction "4_4") (pintype "passive+no_connect"))
    )
    (net (code "93") (name "unconnected-(K10-Pad4)") (class "Default")
      (node (ref "K10") (pin "4") (pinfunction "4_4") (pintype "passive+no_connect"))
    )
    (net (code "94") (name "unconnected-(K11-Pad4)") (class "Default")
      (node (ref "K11") (pin "4") (pinfunction "4_4") (pintype "passive+no_connect"))
    )
    (net (code "95") (name "unconnected-(K12-Pad4)") (class "Default")
      (node (ref "K12") (pin "4") (pinfunction "4_4") (pintype "passive+no_connect"))
    )
    (net (code "96") (name "unconnected-(K13-Pad4)") (class "Default")
      (node (ref "K13") (pin "4") (pinfunction "4_4") (pintype "passive+no_connect"))
    )
    (net (code "97") (name "unconnected-(K14-Pad4)") (class "Default")
      (node (ref "K14") (pin "4") (pinfunction "4_4") (pintype "passive+no_connect"))
    )
    (net (code "98") (name "unconnected-(K15-Pad4)") (class "Default")
      (node (ref "K15") (pin "4") (pinfunction "4_4") (pintype "passive+no_connect"))
    )
    (net (code "99") (name "unconnected-(K16-Pad4)") (class "Default")
      (node (ref "K16") (pin "4") (pinfunction "4_4") (pintype "passive+no_connect"))
    )
  )
)
